# GroundsCoupling.net
KiCad netlist of a schematic drawn in Altium Designer
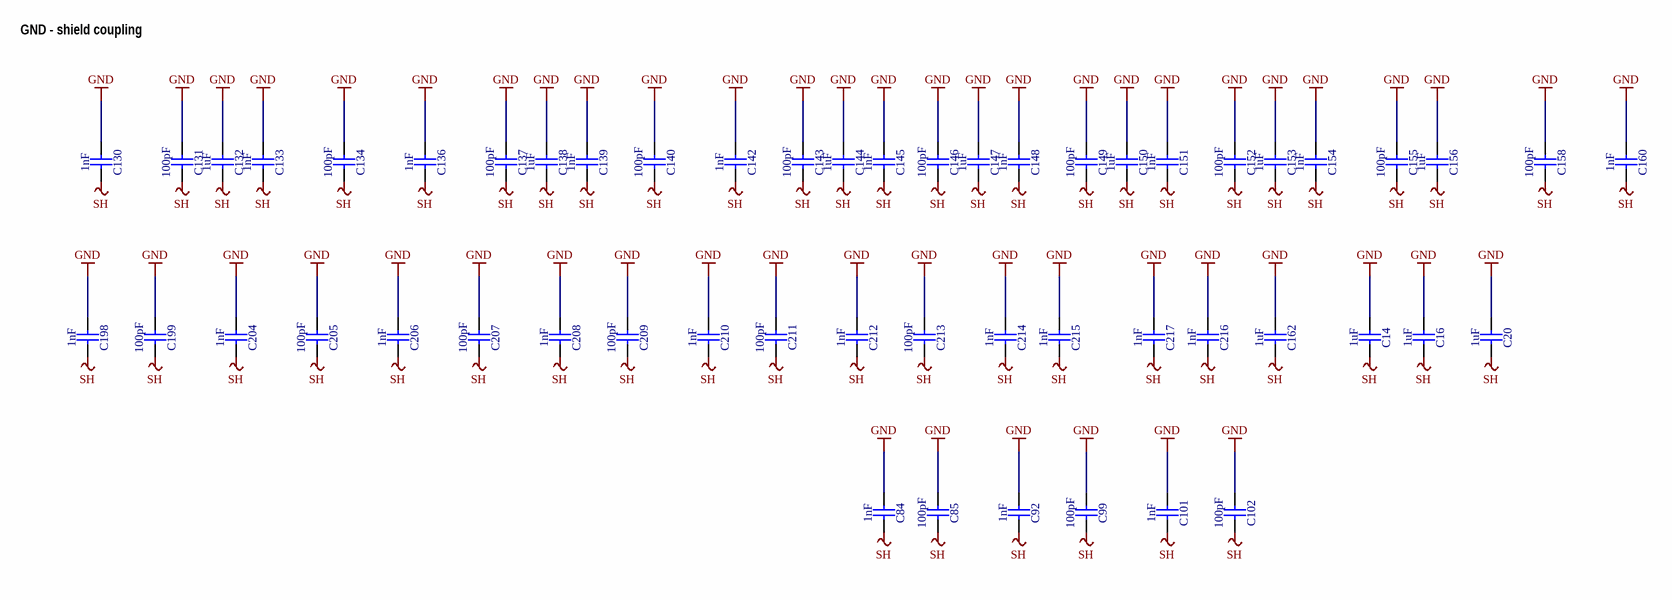
[diagram p0: GroundsCoupling.SchDoc]

(export (version "E")
  (design (tool "Eeschema 10.0.6"))
  (components
    (comp (ref "C14")
      (value "1uF")
      (footprint "CAPC3216X140N")
      (description "Non-polarised capacitor")
      (fields
        (field (name "PART NUMBER") "CC1206_1UF_50V_10%_X7R")
        (field (name "VOLTAGE") "50V")
        (field (name "AUTHOR") "CERN DEM JLC")
      )
      (libsource (lib "Capacitors") (part "Capacitor - non polarized"))
    )
    (comp (ref "C16")
      (value "1uF")
      (footprint "CAPC3216X140N")
      (description "Non-polarised capacitor")
      (fields
        (field (name "PART NUMBER") "CC1206_1UF_50V_10%_X7R")
        (field (name "VOLTAGE") "50V")
        (field (name "AUTHOR") "CERN DEM JLC")
      )
      (libsource (lib "Capacitors") (part "Capacitor - non polarized"))
    )
    (comp (ref "C20")
      (value "1uF")
      (footprint "CAPC3216X140N")
      (description "Non-polarised capacitor")
      (fields
        (field (name "PART NUMBER") "CC1206_1UF_50V_10%_X7R")
        (field (name "VOLTAGE") "50V")
        (field (name "AUTHOR") "CERN DEM JLC")
      )
      (libsource (lib "Capacitors") (part "Capacitor - non polarized"))
    )
    (comp (ref "C84")
      (value "1nF")
      (footprint "CAPC1005X55N")
      (description "Non-polarised capacitor")
      (fields
        (field (name "PART NUMBER") "CC0402_1NF_50V_10%_X7R")
        (field (name "VOLTAGE") "50V")
        (field (name "AUTHOR") "CERN DEM JLC")
      )
      (libsource (lib "Capacitors") (part "Capacitor - non polarized"))
    )
    (comp (ref "C85")
      (value "100pF")
      (footprint "CAPC1005X55N")
      (description "Non-polarised capacitor")
      (fields
        (field (name "PART NUMBER") "CC0402_100PF_50V_5%_C0G")
        (field (name "VOLTAGE") "50V")
        (field (name "AUTHOR") "CERN DEM JLC")
      )
      (libsource (lib "Capacitors") (part "Capacitor - non polarized"))
    )
    (comp (ref "C92")
      (value "1nF")
      (footprint "CAPC1005X55N")
      (description "Non-polarised capacitor")
      (fields
        (field (name "PART NUMBER") "CC0402_1NF_50V_10%_X7R")
        (field (name "VOLTAGE") "50V")
        (field (name "AUTHOR") "CERN DEM JLC")
      )
      (libsource (lib "Capacitors") (part "Capacitor - non polarized"))
    )
    (comp (ref "C99")
      (value "100pF")
      (footprint "CAPC1005X55N")
      (description "Non-polarised capacitor")
      (fields
        (field (name "PART NUMBER") "CC0402_100PF_50V_5%_C0G")
        (field (name "VOLTAGE") "50V")
        (field (name "AUTHOR") "CERN DEM JLC")
      )
      (libsource (lib "Capacitors") (part "Capacitor - non polarized"))
    )
    (comp (ref "C101")
      (value "1nF")
      (footprint "CAPC1005X55N")
      (description "Non-polarised capacitor")
      (fields
        (field (name "PART NUMBER") "CC0402_1NF_50V_10%_X7R")
        (field (name "VOLTAGE") "50V")
        (field (name "AUTHOR") "CERN DEM JLC")
      )
      (libsource (lib "Capacitors") (part "Capacitor - non polarized"))
    )
    (comp (ref "C102")
      (value "100pF")
      (footprint "CAPC1005X55N")
      (description "Non-polarised capacitor")
      (fields
        (field (name "PART NUMBER") "CC0402_100PF_50V_5%_C0G")
        (field (name "VOLTAGE") "50V")
        (field (name "AUTHOR") "CERN DEM JLC")
      )
      (libsource (lib "Capacitors") (part "Capacitor - non polarized"))
    )
    (comp (ref "C130")
      (value "1nF")
      (footprint "CAPC1005X55N")
      (description "Non-polarised capacitor")
      (fields
        (field (name "PART NUMBER") "CC0402_1NF_50V_10%_X7R")
        (field (name "VOLTAGE") "50V")
        (field (name "AUTHOR") "CERN DEM JLC")
      )
      (libsource (lib "Capacitors") (part "Capacitor - non polarized"))
    )
    (comp (ref "C131")
      (value "100pF")
      (footprint "CAPC1005X55N")
      (description "Non-polarised capacitor")
      (fields
        (field (name "PART NUMBER") "CC0402_100PF_50V_5%_C0G")
        (field (name "VOLTAGE") "50V")
        (field (name "AUTHOR") "CERN DEM JLC")
      )
      (libsource (lib "Capacitors") (part "Capacitor - non polarized"))
    )
    (comp (ref "C132")
      (value "1uF")
      (footprint "CAPC3216X140N")
      (description "Non-polarised capacitor")
      (fields
        (field (name "PART NUMBER") "CC1206_1UF_50V_10%_X7R")
        (field (name "VOLTAGE") "50V")
        (field (name "AUTHOR") "CERN DEM JLC")
      )
      (libsource (lib "Capacitors") (part "Capacitor - non polarized"))
    )
    (comp (ref "C133")
      (value "1nF")
      (footprint "CAPC1005X55N")
      (description "Non-polarised capacitor")
      (fields
        (field (name "PART NUMBER") "CC0402_1NF_50V_10%_X7R")
        (field (name "VOLTAGE") "50V")
        (field (name "AUTHOR") "CERN DEM JLC")
      )
      (libsource (lib "Capacitors") (part "Capacitor - non polarized"))
    )
    (comp (ref "C134")
      (value "100pF")
      (footprint "CAPC1005X55N")
      (description "Non-polarised capacitor")
      (fields
        (field (name "PART NUMBER") "CC0402_100PF_50V_5%_C0G")
        (field (name "VOLTAGE") "50V")
        (field (name "AUTHOR") "CERN DEM JLC")
      )
      (libsource (lib "Capacitors") (part "Capacitor - non polarized"))
    )
    (comp (ref "C136")
      (value "1nF")
      (footprint "CAPC1005X55N")
      (description "Non-polarised capacitor")
      (fields
        (field (name "PART NUMBER") "CC0402_1NF_50V_10%_X7R")
        (field (name "VOLTAGE") "50V")
        (field (name "AUTHOR") "CERN DEM JLC")
      )
      (libsource (lib "Capacitors") (part "Capacitor - non polarized"))
    )
    (comp (ref "C137")
      (value "100pF")
      (footprint "CAPC1005X55N")
      (description "Non-polarised capacitor")
      (fields
        (field (name "PART NUMBER") "CC0402_100PF_50V_5%_C0G")
        (field (name "VOLTAGE") "50V")
        (field (name "AUTHOR") "CERN DEM JLC")
      )
      (libsource (lib "Capacitors") (part "Capacitor - non polarized"))
    )
    (comp (ref "C138")
      (value "1uF")
      (footprint "CAPC3216X140N")
      (description "Non-polarised capacitor")
      (fields
        (field (name "PART NUMBER") "CC1206_1UF_50V_10%_X7R")
        (field (name "VOLTAGE") "50V")
        (field (name "AUTHOR") "CERN DEM JLC")
      )
      (libsource (lib "Capacitors") (part "Capacitor - non polarized"))
    )
    (comp (ref "C139")
      (value "1nF")
      (footprint "CAPC1005X55N")
      (description "Non-polarised capacitor")
      (fields
        (field (name "PART NUMBER") "CC0402_1NF_50V_10%_X7R")
        (field (name "VOLTAGE") "50V")
        (field (name "AUTHOR") "CERN DEM JLC")
      )
      (libsource (lib "Capacitors") (part "Capacitor - non polarized"))
    )
    (comp (ref "C140")
      (value "100pF")
      (footprint "CAPC1005X55N")
      (description "Non-polarised capacitor")
      (fields
        (field (name "PART NUMBER") "CC0402_100PF_50V_5%_C0G")
        (field (name "VOLTAGE") "50V")
        (field (name "AUTHOR") "CERN DEM JLC")
      )
      (libsource (lib "Capacitors") (part "Capacitor - non polarized"))
    )
    (comp (ref "C142")
      (value "1nF")
      (footprint "CAPC1005X55N")
      (description "Non-polarised capacitor")
      (fields
        (field (name "PART NUMBER") "CC0402_1NF_50V_10%_X7R")
        (field (name "VOLTAGE") "50V")
        (field (name "AUTHOR") "CERN DEM JLC")
      )
      (libsource (lib "Capacitors") (part "Capacitor - non polarized"))
    )
    (comp (ref "C143")
      (value "100pF")
      (footprint "CAPC1005X55N")
      (description "Non-polarised capacitor")
      (fields
        (field (name "PART NUMBER") "CC0402_100PF_50V_5%_C0G")
        (field (name "VOLTAGE") "50V")
        (field (name "AUTHOR") "CERN DEM JLC")
      )
      (libsource (lib "Capacitors") (part "Capacitor - non polarized"))
    )
    (comp (ref "C144")
      (value "1uF")
      (footprint "CAPC3216X140N")
      (description "Non-polarised capacitor")
      (fields
        (field (name "PART NUMBER") "CC1206_1UF_50V_10%_X7R")
        (field (name "VOLTAGE") "50V")
        (field (name "AUTHOR") "CERN DEM JLC")
      )
      (libsource (lib "Capacitors") (part "Capacitor - non polarized"))
    )
    (comp (ref "C145")
      (value "1nF")
      (footprint "CAPC1005X55N")
      (description "Non-polarised capacitor")
      (fields
        (field (name "PART NUMBER") "CC0402_1NF_50V_10%_X7R")
        (field (name "VOLTAGE") "50V")
        (field (name "AUTHOR") "CERN DEM JLC")
      )
      (libsource (lib "Capacitors") (part "Capacitor - non polarized"))
    )
    (comp (ref "C146")
      (value "100pF")
      (footprint "CAPC1005X55N")
      (description "Non-polarised capacitor")
      (fields
        (field (name "PART NUMBER") "CC0402_100PF_50V_5%_C0G")
        (field (name "VOLTAGE") "50V")
        (field (name "AUTHOR") "CERN DEM JLC")
      )
      (libsource (lib "Capacitors") (part "Capacitor - non polarized"))
    )
    (comp (ref "C147")
      (value "1uF")
      (footprint "CAPC3216X140N")
      (description "Non-polarised capacitor")
      (fields
        (field (name "PART NUMBER") "CC1206_1UF_50V_10%_X7R")
        (field (name "VOLTAGE") "50V")
        (field (name "AUTHOR") "CERN DEM JLC")
      )
      (libsource (lib "Capacitors") (part "Capacitor - non polarized"))
    )
    (comp (ref "C148")
      (value "1nF")
      (footprint "CAPC1005X55N")
      (description "Non-polarised capacitor")
      (fields
        (field (name "PART NUMBER") "CC0402_1NF_50V_10%_X7R")
        (field (name "VOLTAGE") "50V")
        (field (name "AUTHOR") "CERN DEM JLC")
      )
      (libsource (lib "Capacitors") (part "Capacitor - non polarized"))
    )
    (comp (ref "C149")
      (value "100pF")
      (footprint "CAPC1005X55N")
      (description "Non-polarised capacitor")
      (fields
        (field (name "PART NUMBER") "CC0402_100PF_50V_5%_C0G")
        (field (name "VOLTAGE") "50V")
        (field (name "AUTHOR") "CERN DEM JLC")
      )
      (libsource (lib "Capacitors") (part "Capacitor - non polarized"))
    )
    (comp (ref "C150")
      (value "1uF")
      (footprint "CAPC3216X140N")
      (description "Non-polarised capacitor")
      (fields
        (field (name "PART NUMBER") "CC1206_1UF_50V_10%_X7R")
        (field (name "VOLTAGE") "50V")
        (field (name "AUTHOR") "CERN DEM JLC")
      )
      (libsource (lib "Capacitors") (part "Capacitor - non polarized"))
    )
    (comp (ref "C151")
      (value "1nF")
      (footprint "CAPC1005X55N")
      (description "Non-polarised capacitor")
      (fields
        (field (name "PART NUMBER") "CC0402_1NF_50V_10%_X7R")
        (field (name "VOLTAGE") "50V")
        (field (name "AUTHOR") "CERN DEM JLC")
      )
      (libsource (lib "Capacitors") (part "Capacitor - non polarized"))
    )
    (comp (ref "C152")
      (value "100pF")
      (footprint "CAPC1005X55N")
      (description "Non-polarised capacitor")
      (fields
        (field (name "PART NUMBER") "CC0402_100PF_50V_5%_C0G")
        (field (name "VOLTAGE") "50V")
        (field (name "AUTHOR") "CERN DEM JLC")
      )
      (libsource (lib "Capacitors") (part "Capacitor - non polarized"))
    )
    (comp (ref "C153")
      (value "1uF")
      (footprint "CAPC3216X140N")
      (description "Non-polarised capacitor")
      (fields
        (field (name "PART NUMBER") "CC1206_1UF_50V_10%_X7R")
        (field (name "VOLTAGE") "50V")
        (field (name "AUTHOR") "CERN DEM JLC")
      )
      (libsource (lib "Capacitors") (part "Capacitor - non polarized"))
    )
    (comp (ref "C154")
      (value "1nF")
      (footprint "CAPC1005X55N")
      (description "Non-polarised capacitor")
      (fields
        (field (name "PART NUMBER") "CC0402_1NF_50V_10%_X7R")
        (field (name "VOLTAGE") "50V")
        (field (name "AUTHOR") "CERN DEM JLC")
      )
      (libsource (lib "Capacitors") (part "Capacitor - non polarized"))
    )
    (comp (ref "C155")
      (value "100pF")
      (footprint "CAPC1005X55N")
      (description "Non-polarised capacitor")
      (fields
        (field (name "PART NUMBER") "CC0402_100PF_50V_5%_C0G")
        (field (name "VOLTAGE") "50V")
        (field (name "AUTHOR") "CERN DEM JLC")
      )
      (libsource (lib "Capacitors") (part "Capacitor - non polarized"))
    )
    (comp (ref "C156")
      (value "1uF")
      (footprint "CAPC3216X140N")
      (description "Non-polarised capacitor")
      (fields
        (field (name "PART NUMBER") "CC1206_1UF_50V_10%_X7R")
        (field (name "VOLTAGE") "50V")
        (field (name "AUTHOR") "CERN DEM JLC")
      )
      (libsource (lib "Capacitors") (part "Capacitor - non polarized"))
    )
    (comp (ref "C158")
      (value "100pF")
      (footprint "CAPC1005X55N")
      (description "Non-polarised capacitor")
      (fields
        (field (name "PART NUMBER") "CC0402_100PF_50V_5%_C0G")
        (field (name "VOLTAGE") "50V")
        (field (name "AUTHOR") "CERN DEM JLC")
      )
      (libsource (lib "Capacitors") (part "Capacitor - non polarized"))
    )
    (comp (ref "C160")
      (value "1nF")
      (footprint "CAPC1005X55N")
      (description "Non-polarised capacitor")
      (fields
        (field (name "PART NUMBER") "CC0402_1NF_50V_10%_X7R")
        (field (name "VOLTAGE") "50V")
        (field (name "AUTHOR") "CERN DEM JLC")
      )
      (libsource (lib "Capacitors") (part "Capacitor - non polarized"))
    )
    (comp (ref "C162")
      (value "1uF")
      (footprint "CAPC3216X140N")
      (description "Non-polarised capacitor")
      (fields
        (field (name "PART NUMBER") "CC1206_1UF_50V_10%_X7R")
        (field (name "VOLTAGE") "50V")
        (field (name "AUTHOR") "CERN DEM JLC")
      )
      (libsource (lib "Capacitors") (part "Capacitor - non polarized"))
    )
    (comp (ref "C198")
      (value "1nF")
      (footprint "CAPC1005X55N")
      (description "Non-polarised capacitor")
      (fields
        (field (name "PART NUMBER") "CC0402_1NF_50V_10%_X7R")
        (field (name "VOLTAGE") "50V")
        (field (name "AUTHOR") "CERN DEM JLC")
      )
      (libsource (lib "Capacitors") (part "Capacitor - non polarized"))
    )
    (comp (ref "C199")
      (value "100pF")
      (footprint "CAPC1005X55N")
      (description "Non-polarised capacitor")
      (fields
        (field (name "PART NUMBER") "CC0402_100PF_50V_5%_C0G")
        (field (name "VOLTAGE") "50V")
        (field (name "AUTHOR") "CERN DEM JLC")
      )
      (libsource (lib "Capacitors") (part "Capacitor - non polarized"))
    )
    (comp (ref "C204")
      (value "1nF")
      (footprint "CAPC1005X55N")
      (description "Non-polarised capacitor")
      (fields
        (field (name "PART NUMBER") "CC0402_1NF_50V_10%_X7R")
        (field (name "VOLTAGE") "50V")
        (field (name "AUTHOR") "CERN DEM JLC")
      )
      (libsource (lib "Capacitors") (part "Capacitor - non polarized"))
    )
    (comp (ref "C205")
      (value "100pF")
      (footprint "CAPC1005X55N")
      (description "Non-polarised capacitor")
      (fields
        (field (name "PART NUMBER") "CC0402_100PF_50V_5%_C0G")
        (field (name "VOLTAGE") "50V")
        (field (name "AUTHOR") "CERN DEM JLC")
      )
      (libsource (lib "Capacitors") (part "Capacitor - non polarized"))
    )
    (comp (ref "C206")
      (value "1nF")
      (footprint "CAPC1005X55N")
      (description "Non-polarised capacitor")
      (fields
        (field (name "PART NUMBER") "CC0402_1NF_50V_10%_X7R")
        (field (name "VOLTAGE") "50V")
        (field (name "AUTHOR") "CERN DEM JLC")
      )
      (libsource (lib "Capacitors") (part "Capacitor - non polarized"))
    )
    (comp (ref "C207")
      (value "100pF")
      (footprint "CAPC1005X55N")
      (description "Non-polarised capacitor")
      (fields
        (field (name "PART NUMBER") "CC0402_100PF_50V_5%_C0G")
        (field (name "VOLTAGE") "50V")
        (field (name "AUTHOR") "CERN DEM JLC")
      )
      (libsource (lib "Capacitors") (part "Capacitor - non polarized"))
    )
    (comp (ref "C208")
      (value "1nF")
      (footprint "CAPC1005X55N")
      (description "Non-polarised capacitor")
      (fields
        (field (name "PART NUMBER") "CC0402_1NF_50V_10%_X7R")
        (field (name "VOLTAGE") "50V")
        (field (name "AUTHOR") "CERN DEM JLC")
      )
      (libsource (lib "Capacitors") (part "Capacitor - non polarized"))
    )
    (comp (ref "C209")
      (value "100pF")
      (footprint "CAPC1005X55N")
      (description "Non-polarised capacitor")
      (fields
        (field (name "PART NUMBER") "CC0402_100PF_50V_5%_C0G")
        (field (name "VOLTAGE") "50V")
        (field (name "AUTHOR") "CERN DEM JLC")
      )
      (libsource (lib "Capacitors") (part "Capacitor - non polarized"))
    )
    (comp (ref "C210")
      (value "1nF")
      (footprint "CAPC1005X55N")
      (description "Non-polarised capacitor")
      (fields
        (field (name "PART NUMBER") "CC0402_1NF_50V_10%_X7R")
        (field (name "VOLTAGE") "50V")
        (field (name "AUTHOR") "CERN DEM JLC")
      )
      (libsource (lib "Capacitors") (part "Capacitor - non polarized"))
    )
    (comp (ref "C211")
      (value "100pF")
      (footprint "CAPC1005X55N")
      (description "Non-polarised capacitor")
      (fields
        (field (name "PART NUMBER") "CC0402_100PF_50V_5%_C0G")
        (field (name "VOLTAGE") "50V")
        (field (name "AUTHOR") "CERN DEM JLC")
      )
      (libsource (lib "Capacitors") (part "Capacitor - non polarized"))
    )
    (comp (ref "C212")
      (value "1nF")
      (footprint "CAPC1005X55N")
      (description "Non-polarised capacitor")
      (fields
        (field (name "PART NUMBER") "CC0402_1NF_50V_10%_X7R")
        (field (name "VOLTAGE") "50V")
        (field (name "AUTHOR") "CERN DEM JLC")
      )
      (libsource (lib "Capacitors") (part "Capacitor - non polarized"))
    )
    (comp (ref "C213")
      (value "100pF")
      (footprint "CAPC1005X55N")
      (description "Non-polarised capacitor")
      (fields
        (field (name "PART NUMBER") "CC0402_100PF_50V_5%_C0G")
        (field (name "VOLTAGE") "50V")
        (field (name "AUTHOR") "CERN DEM JLC")
      )
      (libsource (lib "Capacitors") (part "Capacitor - non polarized"))
    )
    (comp (ref "C214")
      (value "1nF")
      (footprint "CAPC1005X55N")
      (description "Non-polarised capacitor")
      (fields
        (field (name "PART NUMBER") "CC0402_1NF_50V_10%_X7R")
        (field (name "VOLTAGE") "50V")
        (field (name "AUTHOR") "CERN DEM JLC")
      )
      (libsource (lib "Capacitors") (part "Capacitor - non polarized"))
    )
    (comp (ref "C215")
      (value "1nF")
      (footprint "CAPC1005X55N")
      (description "Non-polarised capacitor")
      (fields
        (field (name "PART NUMBER") "CC0402_1NF_50V_10%_X7R")
        (field (name "VOLTAGE") "50V")
        (field (name "AUTHOR") "CERN DEM JLC")
      )
      (libsource (lib "Capacitors") (part "Capacitor - non polarized"))
    )
    (comp (ref "C216")
      (value "1nF")
      (footprint "CAPC1005X55N")
      (description "Non-polarised capacitor")
      (fields
        (field (name "PART NUMBER") "CC0402_1NF_50V_10%_X7R")
        (field (name "VOLTAGE") "50V")
        (field (name "AUTHOR") "CERN DEM JLC")
      )
      (libsource (lib "Capacitors") (part "Capacitor - non polarized"))
    )
    (comp (ref "C217")
      (value "1nF")
      (footprint "CAPC1005X55N")
      (description "Non-polarised capacitor")
      (fields
        (field (name "PART NUMBER") "CC0402_1NF_50V_10%_X7R")
        (field (name "VOLTAGE") "50V")
        (field (name "AUTHOR") "CERN DEM JLC")
      )
      (libsource (lib "Capacitors") (part "Capacitor - non polarized"))
    )
  )
  (nets
    (net (code "1") (name "GND") (class "Default")
      (node (ref "C101") (pin "1") (pinfunction "1_1") (pintype "passive"))
      (node (ref "C102") (pin "1") (pinfunction "1_1") (pintype "passive"))
      (node (ref "C130") (pin "1") (pinfunction "1_1") (pintype "passive"))
      (node (ref "C131") (pin "1") (pinfunction "1_1") (pintype "passive"))
      (node (ref "C132") (pin "1") (pinfunction "1_1") (pintype "passive"))
      (node (ref "C133") (pin "1") (pinfunction "1_1") (pintype "passive"))
      (node (ref "C134") (pin "1") (pinfunction "1_1") (pintype "passive"))
      (node (ref "C136") (pin "1") (pinfunction "1_1") (pintype "passive"))
      (node (ref "C137") (pin "1") (pinfunction "1_1") (pintype "passive"))
      (node (ref "C138") (pin "1") (pinfunction "1_1") (pintype "passive"))
      (node (ref "C139") (pin "1") (pinfunction "1_1") (pintype "passive"))
      (node (ref "C14") (pin "1") (pinfunction "1_1") (pintype "passive"))
      (node (ref "C140") (pin "1") (pinfunction "1_1") (pintype "passive"))
      (node (ref "C142") (pin "1") (pinfunction "1_1") (pintype "passive"))
      (node (ref "C143") (pin "1") (pinfunction "1_1") (pintype "passive"))
      (node (ref "C144") (pin "1") (pinfunction "1_1") (pintype "passive"))
      (node (ref "C145") (pin "1") (pinfunction "1_1") (pintype "passive"))
      (node (ref "C146") (pin "1") (pinfunction "1_1") (pintype "passive"))
      (node (ref "C147") (pin "1") (pinfunction "1_1") (pintype "passive"))
      (node (ref "C148") (pin "1") (pinfunction "1_1") (pintype "passive"))
      (node (ref "C149") (pin "1") (pinfunction "1_1") (pintype "passive"))
      (node (ref "C150") (pin "1") (pinfunction "1_1") (pintype "passive"))
      (node (ref "C151") (pin "1") (pinfunction "1_1") (pintype "passive"))
      (node (ref "C152") (pin "1") (pinfunction "1_1") (pintype "passive"))
      (node (ref "C153") (pin "1") (pinfunction "1_1") (pintype "passive"))
      (node (ref "C154") (pin "1") (pinfunction "1_1") (pintype "passive"))
      (node (ref "C155") (pin "1") (pinfunction "1_1") (pintype "passive"))
      (node (ref "C156") (pin "1") (pinfunction "1_1") (pintype "passive"))
      (node (ref "C158") (pin "1") (pinfunction "1_1") (pintype "passive"))
      (node (ref "C16") (pin "1") (pinfunction "1_1") (pintype "passive"))
      (node (ref "C160") (pin "1") (pinfunction "1_1") (pintype "passive"))
      (node (ref "C162") (pin "1") (pinfunction "1_1") (pintype "passive"))
      (node (ref "C198") (pin "1") (pinfunction "1_1") (pintype "passive"))
      (node (ref "C199") (pin "1") (pinfunction "1_1") (pintype "passive"))
      (node (ref "C20") (pin "1") (pinfunction "1_1") (pintype "passive"))
      (node (ref "C204") (pin "1") (pinfunction "1_1") (pintype "passive"))
      (node (ref "C205") (pin "1") (pinfunction "1_1") (pintype "passive"))
      (node (ref "C206") (pin "1") (pinfunction "1_1") (pintype "passive"))
      (node (ref "C207") (pin "1") (pinfunction "1_1") (pintype "passive"))
      (node (ref "C208") (pin "1") (pinfunction "1_1") (pintype "passive"))
      (node (ref "C209") (pin "1") (pinfunction "1_1") (pintype "passive"))
      (node (ref "C210") (pin "1") (pinfunction "1_1") (pintype "passive"))
      (node (ref "C211") (pin "1") (pinfunction "1_1") (pintype "passive"))
      (node (ref "C212") (pin "1") (pinfunction "1_1") (pintype "passive"))
      (node (ref "C213") (pin "1") (pinfunction "1_1") (pintype "passive"))
      (node (ref "C214") (pin "1") (pinfunction "1_1") (pintype "passive"))
      (node (ref "C215") (pin "1") (pinfunction "1_1") (pintype "passive"))
      (node (ref "C216") (pin "1") (pinfunction "1_1") (pintype "passive"))
      (node (ref "C217") (pin "1") (pinfunction "1_1") (pintype "passive"))
      (node (ref "C84") (pin "1") (pinfunction "1_1") (pintype "passive"))
      (node (ref "C85") (pin "1") (pinfunction "1_1") (pintype "passive"))
      (node (ref "C92") (pin "1") (pinfunction "1_1") (pintype "passive"))
      (node (ref "C99") (pin "1") (pinfunction "1_1") (pintype "passive"))
    )
    (net (code "2") (name "SH") (class "Default")
      (node (ref "C101") (pin "2") (pinfunction "2_2") (pintype "passive"))
      (node (ref "C102") (pin "2") (pinfunction "2_2") (pintype "passive"))
      (node (ref "C130") (pin "2") (pinfunction "2_2") (pintype "passive"))
      (node (ref "C131") (pin "2") (pinfunction "2_2") (pintype "passive"))
      (node (ref "C132") (pin "2") (pinfunction "2_2") (pintype "passive"))
      (node (ref "C133") (pin "2") (pinfunction "2_2") (pintype "passive"))
      (node (ref "C134") (pin "2") (pinfunction "2_2") (pintype "passive"))
      (node (ref "C136") (pin "2") (pinfunction "2_2") (pintype "passive"))
      (node (ref "C137") (pin "2") (pinfunction "2_2") (pintype "passive"))
      (node (ref "C138") (pin "2") (pinfunction "2_2") (pintype "passive"))
      (node (ref "C139") (pin "2") (pinfunction "2_2") (pintype "passive"))
      (node (ref "C14") (pin "2") (pinfunction "2_2") (pintype "passive"))
      (node (ref "C140") (pin "2") (pinfunction "2_2") (pintype "passive"))
      (node (ref "C142") (pin "2") (pinfunction "2_2") (pintype "passive"))
      (node (ref "C143") (pin "2") (pinfunction "2_2") (pintype "passive"))
      (node (ref "C144") (pin "2") (pinfunction "2_2") (pintype "passive"))
      (node (ref "C145") (pin "2") (pinfunction "2_2") (pintype "passive"))
      (node (ref "C146") (pin "2") (pinfunction "2_2") (pintype "passive"))
      (node (ref "C147") (pin "2") (pinfunction "2_2") (pintype "passive"))
      (node (ref "C148") (pin "2") (pinfunction "2_2") (pintype "passive"))
      (node (ref "C149") (pin "2") (pinfunction "2_2") (pintype "passive"))
      (node (ref "C150") (pin "2") (pinfunction "2_2") (pintype "passive"))
      (node (ref "C151") (pin "2") (pinfunction "2_2") (pintype "passive"))
      (node (ref "C152") (pin "2") (pinfunction "2_2") (pintype "passive"))
      (node (ref "C153") (pin "2") (pinfunction "2_2") (pintype "passive"))
      (node (ref "C154") (pin "2") (pinfunction "2_2") (pintype "passive"))
      (node (ref "C155") (pin "2") (pinfunction "2_2") (pintype "passive"))
      (node (ref "C156") (pin "2") (pinfunction "2_2") (pintype "passive"))
      (node (ref "C158") (pin "2") (pinfunction "2_2") (pintype "passive"))
      (node (ref "C16") (pin "2") (pinfunction "2_2") (pintype "passive"))
      (node (ref "C160") (pin "2") (pinfunction "2_2") (pintype "passive"))
      (node (ref "C162") (pin "2") (pinfunction "2_2") (pintype "passive"))
      (node (ref "C198") (pin "2") (pinfunction "2_2") (pintype "passive"))
      (node (ref "C199") (pin "2") (pinfunction "2_2") (pintype "passive"))
      (node (ref "C20") (pin "2") (pinfunction "2_2") (pintype "passive"))
      (node (ref "C204") (pin "2") (pinfunction "2_2") (pintype "passive"))
      (node (ref "C205") (pin "2") (pinfunction "2_2") (pintype "passive"))
      (node (ref "C206") (pin "2") (pinfunction "2_2") (pintype "passive"))
      (node (ref "C207") (pin "2") (pinfunction "2_2") (pintype "passive"))
      (node (ref "C208") (pin "2") (pinfunction "2_2") (pintype "passive"))
      (node (ref "C209") (pin "2") (pinfunction "2_2") (pintype "passive"))
      (node (ref "C210") (pin "2") (pinfunction "2_2") (pintype "passive"))
      (node (ref "C211") (pin "2") (pinfunction "2_2") (pintype "passive"))
      (node (ref "C212") (pin "2") (pinfunction "2_2") (pintype "passive"))
      (node (ref "C213") (pin "2") (pinfunction "2_2") (pintype "passive"))
      (node (ref "C214") (pin "2") (pinfunction "2_2") (pintype "passive"))
      (node (ref "C215") (pin "2") (pinfunction "2_2") (pintype "passive"))
      (node (ref "C216") (pin "2") (pinfunction "2_2") (pintype "passive"))
      (node (ref "C217") (pin "2") (pinfunction "2_2") (pintype "passive"))
      (node (ref "C84") (pin "2") (pinfunction "2_2") (pintype "passive"))
      (node (ref "C85") (pin "2") (pinfunction "2_2") (pintype "passive"))
      (node (ref "C92") (pin "2") (pinfunction "2_2") (pintype "passive"))
      (node (ref "C99") (pin "2") (pinfunction "2_2") (pintype "passive"))
    )
  )
)
